# FPC.net
KiCad netlist of a schematic drawn in EasyEDA Pro
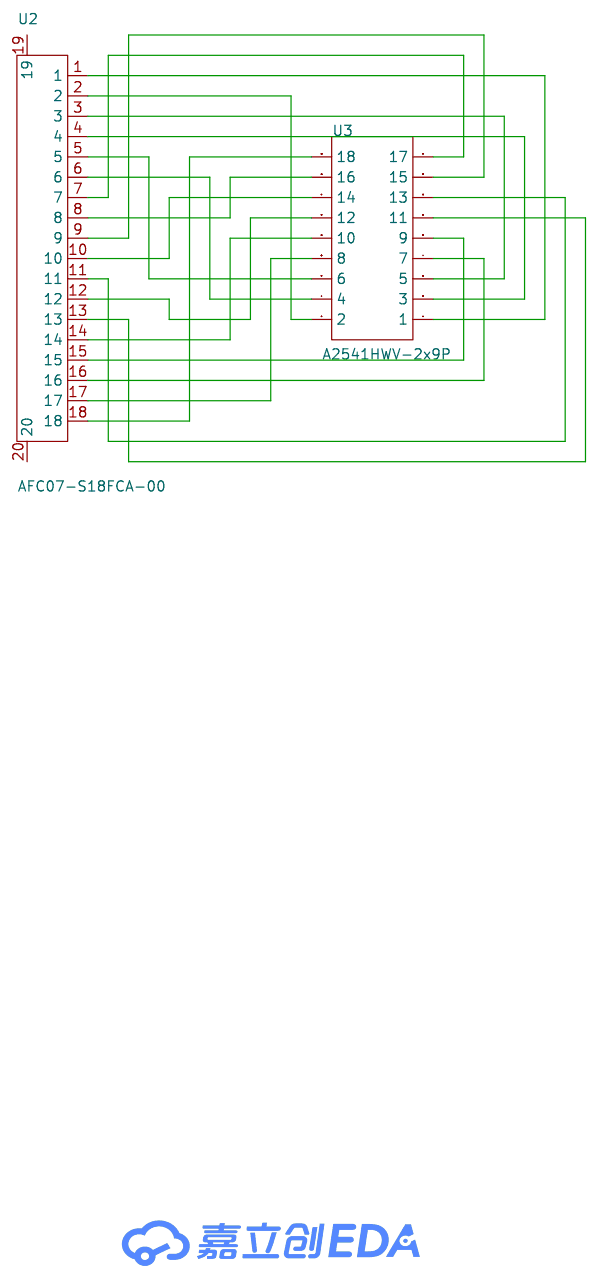
[diagram p0: schematic sheet]

(export (version "E")
  (design (tool "Eeschema 10.0.6"))
  (components
    (comp (ref "U2")
      (value "AFC07-S18FCA-00")
      (footprint "easyedapro:CONN-SMD_18P-P1.00_FFC1.0-18")
      (fields (field (name "Manufacturer") "JS(钜硕电子)"))
      (libsource (lib "easyedapro") (part "FFC1.0-18"))
    )
    (comp (ref "U3")
      (value "A2541HWV-2x9P")
      (footprint "easyedapro:HDR-TH_18P-P2.54-V-F-R2-C9-S2.54-1")
      (fields (field (name "Manufacturer") "CJT(长江连接器)"))
      (libsource (lib "easyedapro") (part "A2541HWV-2X9P_C5362477"))
    )
  )
  (nets
    (net (code "1") (name "Net-(U2-Pad1)") (class "Default")
      (node (ref "U2") (pin "1") (pinfunction "1_1") (pintype "unspecified"))
      (node (ref "U3") (pin "1") (pinfunction "1_1") (pintype "input"))
    )
    (net (code "2") (name "Net-(U2-Pad2)") (class "Default")
      (node (ref "U2") (pin "2") (pinfunction "2_2") (pintype "unspecified"))
      (node (ref "U3") (pin "2") (pinfunction "2_2") (pintype "input"))
    )
    (net (code "3") (name "Net-(U2-Pad3)") (class "Default")
      (node (ref "U2") (pin "3") (pinfunction "3_3") (pintype "unspecified"))
      (node (ref "U3") (pin "5") (pinfunction "5_5") (pintype "input"))
    )
    (net (code "4") (name "Net-(U2-Pad4)") (class "Default")
      (node (ref "U2") (pin "4") (pinfunction "4_4") (pintype "unspecified"))
      (node (ref "U3") (pin "3") (pinfunction "3_3") (pintype "input"))
    )
    (net (code "5") (name "Net-(U2-Pad5)") (class "Default")
      (node (ref "U2") (pin "5") (pinfunction "5_5") (pintype "unspecified"))
      (node (ref "U3") (pin "6") (pinfunction "6_6") (pintype "input"))
    )
    (net (code "6") (name "Net-(U2-Pad6)") (class "Default")
      (node (ref "U2") (pin "6") (pinfunction "6_6") (pintype "unspecified"))
      (node (ref "U3") (pin "4") (pinfunction "4_4") (pintype "input"))
    )
    (net (code "7") (name "Net-(U2-Pad7)") (class "Default")
      (node (ref "U2") (pin "7") (pinfunction "7_7") (pintype "unspecified"))
      (node (ref "U3") (pin "17") (pinfunction "17_17") (pintype "input"))
    )
    (net (code "8") (name "Net-(U2-Pad8)") (class "Default")
      (node (ref "U2") (pin "8") (pinfunction "8_8") (pintype "unspecified"))
      (node (ref "U3") (pin "16") (pinfunction "16_16") (pintype "input"))
    )
    (net (code "9") (name "Net-(U2-Pad9)") (class "Default")
      (node (ref "U2") (pin "9") (pinfunction "9_9") (pintype "unspecified"))
      (node (ref "U3") (pin "15") (pinfunction "15_15") (pintype "input"))
    )
    (net (code "10") (name "Net-(U2-Pad10)") (class "Default")
      (node (ref "U2") (pin "10") (pinfunction "10_10") (pintype "unspecified"))
      (node (ref "U3") (pin "14") (pinfunction "14_14") (pintype "input"))
    )
    (net (code "11") (name "Net-(U2-Pad11)") (class "Default")
      (node (ref "U2") (pin "11") (pinfunction "11_11") (pintype "unspecified"))
      (node (ref "U3") (pin "13") (pinfunction "13_13") (pintype "input"))
    )
    (net (code "12") (name "Net-(U2-Pad12)") (class "Default")
      (node (ref "U2") (pin "12") (pinfunction "12_12") (pintype "unspecified"))
      (node (ref "U3") (pin "12") (pinfunction "12_12") (pintype "input"))
    )
    (net (code "13") (name "Net-(U2-Pad13)") (class "Default")
      (node (ref "U2") (pin "13") (pinfunction "13_13") (pintype "unspecified"))
      (node (ref "U3") (pin "11") (pinfunction "11_11") (pintype "input"))
    )
    (net (code "14") (name "Net-(U2-Pad14)") (class "Default")
      (node (ref "U2") (pin "14") (pinfunction "14_14") (pintype "unspecified"))
      (node (ref "U3") (pin "10") (pinfunction "10_10") (pintype "input"))
    )
    (net (code "15") (name "Net-(U2-Pad15)") (class "Default")
      (node (ref "U2") (pin "15") (pinfunction "15_15") (pintype "unspecified"))
      (node (ref "U3") (pin "9") (pinfunction "9_9") (pintype "input"))
    )
    (net (code "16") (name "Net-(U2-Pad16)") (class "Default")
      (node (ref "U2") (pin "16") (pinfunction "16_16") (pintype "unspecified"))
      (node (ref "U3") (pin "7") (pinfunction "7_7") (pintype "input"))
    )
    (net (code "17") (name "Net-(U2-Pad17)") (class "Default")
      (node (ref "U2") (pin "17") (pinfunction "17_17") (pintype "unspecified"))
      (node (ref "U3") (pin "8") (pinfunction "8_8") (pintype "input"))
    )
    (net (code "18") (name "Net-(U2-Pad18)") (class "Default")
      (node (ref "U2") (pin "18") (pinfunction "18_18") (pintype "unspecified"))
      (node (ref "U3") (pin "18") (pinfunction "18_18") (pintype "input"))
    )
    (net (code "19") (name "unconnected-(U2-Pad19)") (class "Default")
      (node (ref "U2") (pin "19") (pinfunction "19_19") (pintype "unspecified"))
    )
    (net (code "20") (name "unconnected-(U2-Pad20)") (class "Default")
      (node (ref "U2") (pin "20") (pinfunction "20_20") (pintype "unspecified"))
    )
  )
)
